# Sheet_1_2021-06-21.net
KiCad netlist of a schematic drawn in Altium Designer
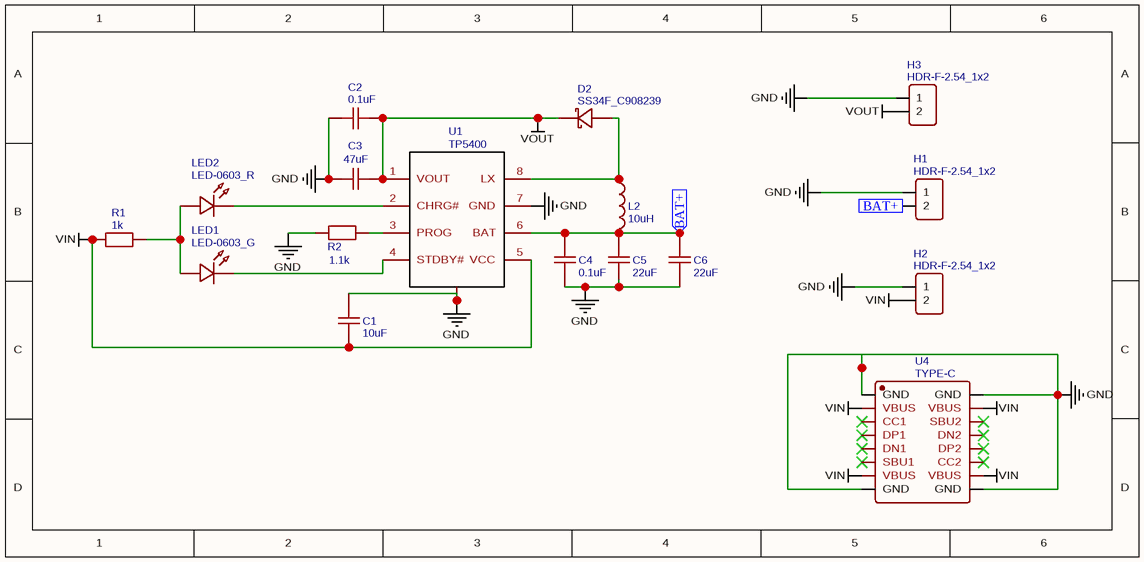
[diagram p0: Sheet_1_2021-06-21.schdoc]

(export (version "E")
  (design (tool "Eeschema 10.0.6"))
  (components
    (comp (ref "C1")
      (value "10uF")
      (fields (field (name "CONTRIBUTOR") "LCEDA_Lib"))
      (libsource (lib "altium-import") (part "root_3_10uF_"))
    )
    (comp (ref "C2")
      (value "0.1uF")
      (fields (field (name "CONTRIBUTOR") "LCEDA_Lib"))
      (libsource (lib "altium-import") (part "root_0_0.1uF_"))
    )
    (comp (ref "C3")
      (value "47uF")
      (fields (field (name "CONTRIBUTOR") "LCEDA_Lib"))
      (libsource (lib "altium-import") (part "root_0_47uF_"))
    )
    (comp (ref "C4")
      (value "0.1uF")
      (fields (field (name "CONTRIBUTOR") "LCEDA_Lib"))
      (libsource (lib "altium-import") (part "root_3_0.1uF_"))
    )
    (comp (ref "C5")
      (value "22uF")
      (fields (field (name "CONTRIBUTOR") "LCEDA_Lib"))
      (libsource (lib "altium-import") (part "root_3_22uF_"))
    )
    (comp (ref "C6")
      (value "22uF")
      (fields (field (name "CONTRIBUTOR") "LCEDA_Lib"))
      (libsource (lib "altium-import") (part "root_3_22uF_"))
    )
    (comp (ref "D2")
      (value "SS34F_C908239")
      (fields
        (field (name "BOM_SUPPLIER PART") "C908239")
        (field (name "BOM_MANUFACTURER PART") "SS34F")
        (field (name "CONTRIBUTOR") "LCSC")
      )
      (libsource (lib "altium-import") (part "root_0_SS34F_C908239_"))
    )
    (comp (ref "H1")
      (value "HDR-F-2.54_1x2")
      (fields (field (name "BOM_SUPPLIER PART") "C49661") (field (name "CONTRIBUTOR") "LCEDA_Lib"))
      (libsource (lib "altium-import") (part "root_0_HDR-F-2.54_1x2_"))
    )
    (comp (ref "H2")
      (value "HDR-F-2.54_1x2")
      (fields (field (name "BOM_SUPPLIER PART") "C49661") (field (name "CONTRIBUTOR") "LCEDA_Lib"))
      (libsource (lib "altium-import") (part "root_0_HDR-F-2.54_1x2_"))
    )
    (comp (ref "H3")
      (value "HDR-F-2.54_1x2")
      (fields (field (name "BOM_SUPPLIER PART") "C49661") (field (name "CONTRIBUTOR") "LCEDA_Lib"))
      (libsource (lib "altium-import") (part "root_0_HDR-F-2.54_1x2_"))
    )
    (comp (ref "L2")
      (value "10uH")
      (fields
        (field (name "BOM_MANUFACTURER PART") "FXL0630-100-M")
        (field (name "BOM_SUPPLIER PART") "C167223")
        (field (name "CONTRIBUTOR") "LCSC")
      )
      (libsource (lib "altium-import") (part "root_3_10uH_"))
    )
    (comp (ref "LED1")
      (value "LED-0603_G")
      (fields
        (field (name "BOM_MANUFACTURER PART") "19-217/GHC-YR1S2/3T")
        (field (name "BOM_SUPPLIER PART") "C72043")
        (field (name "CONTRIBUTOR") "LCEDA_Lib")
      )
      (libsource (lib "altium-import") (part "root_0_LED-0603_G_"))
    )
    (comp (ref "LED2")
      (value "LED-0603_R")
      (fields
        (field (name "BOM_MANUFACTURER PART") "19-217/R6C-AL1M2VY/3T")
        (field (name "BOM_SUPPLIER PART") "C72044")
        (field (name "CONTRIBUTOR") "LCEDA_01")
      )
      (libsource (lib "altium-import") (part "root_0_LED-0603_R_"))
    )
    (comp (ref "R1")
      (value "1k")
      (fields (field (name "CONTRIBUTOR") "LCEDA_Lib"))
      (libsource (lib "altium-import") (part "root_0_1k_"))
    )
    (comp (ref "R2")
      (value "1.1k")
      (fields (field (name "CONTRIBUTOR") "LCEDA_Lib"))
      (libsource (lib "altium-import") (part "root_0_1.1k_"))
    )
    (comp (ref "U1")
      (value "TP5400")
      (fields (field (name "BOM_SUPPLIER PART") "C24154"))
      (libsource (lib "altium-import") (part "root_0_TP5400_"))
    )
    (comp (ref "U4")
      (value "TYPE-C")
      (fields (field (name "CONTRIBUTOR") "WQM_Editor"))
      (libsource (lib "altium-import") (part "root_0_TYPE-C_"))
    )
  )
  (nets
    (net (code "1") (name "/BAT+") (class "Default")
      (node (ref "C4") (pin "1") (pinfunction "1_1") (pintype "passive"))
      (node (ref "C5") (pin "1") (pinfunction "1_1") (pintype "passive"))
      (node (ref "C6") (pin "1") (pinfunction "1_1") (pintype "passive"))
      (node (ref "H1") (pin "2") (pinfunction "2_2") (pintype "passive"))
      (node (ref "L2") (pin "2") (pinfunction "2_2") (pintype "passive"))
      (node (ref "U1") (pin "6") (pinfunction "BAT_6") (pintype "passive"))
    )
    (net (code "2") (name "GND") (class "Default")
      (node (ref "C1") (pin "1") (pinfunction "1_1") (pintype "passive"))
      (node (ref "C2") (pin "1") (pinfunction "1_1") (pintype "passive"))
      (node (ref "C3") (pin "1") (pinfunction "1_1") (pintype "passive"))
      (node (ref "C4") (pin "2") (pinfunction "2_2") (pintype "passive"))
      (node (ref "C5") (pin "2") (pinfunction "2_2") (pintype "passive"))
      (node (ref "C6") (pin "2") (pinfunction "2_2") (pintype "passive"))
      (node (ref "H1") (pin "1") (pinfunction "1_1") (pintype "passive"))
      (node (ref "H2") (pin "1") (pinfunction "1_1") (pintype "passive"))
      (node (ref "H3") (pin "1") (pinfunction "1_1") (pintype "passive"))
      (node (ref "R2") (pin "1") (pinfunction "1_1") (pintype "passive"))
      (node (ref "U1") (pin "7") (pinfunction "GND_7") (pintype "passive"))
      (node (ref "U1") (pin "9") (pinfunction "9_9") (pintype "passive"))
      (node (ref "U4") (pin "A1/B12") (pinfunction "GND_A1/B12") (pintype "passive"))
      (node (ref "U4") (pin "B1/A12") (pinfunction "GND_B1/A12") (pintype "passive"))
    )
    (net (code "3") (name "Net-(D2-A)") (class "Default")
      (node (ref "D2") (pin "1") (pinfunction "A_1") (pintype "passive"))
      (node (ref "L2") (pin "1") (pinfunction "1_1") (pintype "passive"))
      (node (ref "U1") (pin "8") (pinfunction "LX_8") (pintype "passive"))
    )
    (net (code "4") (name "Net-(LED1-Pad1)") (class "Default")
      (node (ref "LED1") (pin "1") (pinfunction "1_1") (pintype "passive"))
      (node (ref "LED2") (pin "1") (pinfunction "1_1") (pintype "passive"))
      (node (ref "R1") (pin "2") (pinfunction "2_2") (pintype "passive"))
    )
    (net (code "5") (name "Net-(U1-CHRG#)") (class "Default")
      (node (ref "LED2") (pin "2") (pinfunction "2_2") (pintype "passive"))
      (node (ref "U1") (pin "2") (pinfunction "CHRG#_2") (pintype "passive"))
    )
    (net (code "6") (name "Net-(U1-PROG)") (class "Default")
      (node (ref "R2") (pin "2") (pinfunction "2_2") (pintype "passive"))
      (node (ref "U1") (pin "3") (pinfunction "PROG_3") (pintype "passive"))
    )
    (net (code "7") (name "Net-(U1-STDBY#)") (class "Default")
      (node (ref "LED1") (pin "2") (pinfunction "2_2") (pintype "passive"))
      (node (ref "U1") (pin "4") (pinfunction "STDBY#_4") (pintype "passive"))
    )
    (net (code "8") (name "VIN") (class "Default")
      (node (ref "C1") (pin "2") (pinfunction "2_2") (pintype "passive"))
      (node (ref "H2") (pin "2") (pinfunction "2_2") (pintype "passive"))
      (node (ref "R1") (pin "1") (pinfunction "1_1") (pintype "passive"))
      (node (ref "U1") (pin "5") (pinfunction "VCC_5") (pintype "passive"))
      (node (ref "U4") (pin "A4/B9") (pinfunction "VBUS_A4/B9") (pintype "passive"))
      (node (ref "U4") (pin "B4/A9") (pinfunction "VBUS_B4/A9") (pintype "passive"))
    )
    (net (code "9") (name "VOUT") (class "Default")
      (node (ref "C2") (pin "2") (pinfunction "2_2") (pintype "passive"))
      (node (ref "C3") (pin "2") (pinfunction "2_2") (pintype "passive"))
      (node (ref "D2") (pin "2") (pinfunction "K_2") (pintype "passive"))
      (node (ref "H3") (pin "2") (pinfunction "2_2") (pintype "passive"))
      (node (ref "U1") (pin "1") (pinfunction "VOUT_1") (pintype "passive"))
    )
    (net (code "10") (name "unconnected-(U4-CC1-PadA5)") (class "Default")
      (node (ref "U4") (pin "A5") (pinfunction "CC1_A5") (pintype "passive+no_connect"))
    )
    (net (code "11") (name "unconnected-(U4-CC2-PadB5)") (class "Default")
      (node (ref "U4") (pin "B5") (pinfunction "CC2_B5") (pintype "passive+no_connect"))
    )
    (net (code "12") (name "unconnected-(U4-DN1-PadA7)") (class "Default")
      (node (ref "U4") (pin "A7") (pinfunction "DN1_A7") (pintype "passive+no_connect"))
    )
    (net (code "13") (name "unconnected-(U4-DN2-PadB7)") (class "Default")
      (node (ref "U4") (pin "B7") (pinfunction "DN2_B7") (pintype "passive+no_connect"))
    )
    (net (code "14") (name "unconnected-(U4-DP1-PadA6)") (class "Default")
      (node (ref "U4") (pin "A6") (pinfunction "DP1_A6") (pintype "passive+no_connect"))
    )
    (net (code "15") (name "unconnected-(U4-DP2-PadB6)") (class "Default")
      (node (ref "U4") (pin "B6") (pinfunction "DP2_B6") (pintype "passive+no_connect"))
    )
    (net (code "16") (name "unconnected-(U4-SBU1-PadA8)") (class "Default")
      (node (ref "U4") (pin "A8") (pinfunction "SBU1_A8") (pintype "passive+no_connect"))
    )
    (net (code "17") (name "unconnected-(U4-SBU2-PadB8)") (class "Default")
      (node (ref "U4") (pin "B8") (pinfunction "SBU2_B8") (pintype "passive+no_connect"))
    )
  )
)
